# VHCDI.net
KiCad netlist of a schematic drawn in Altium Designer
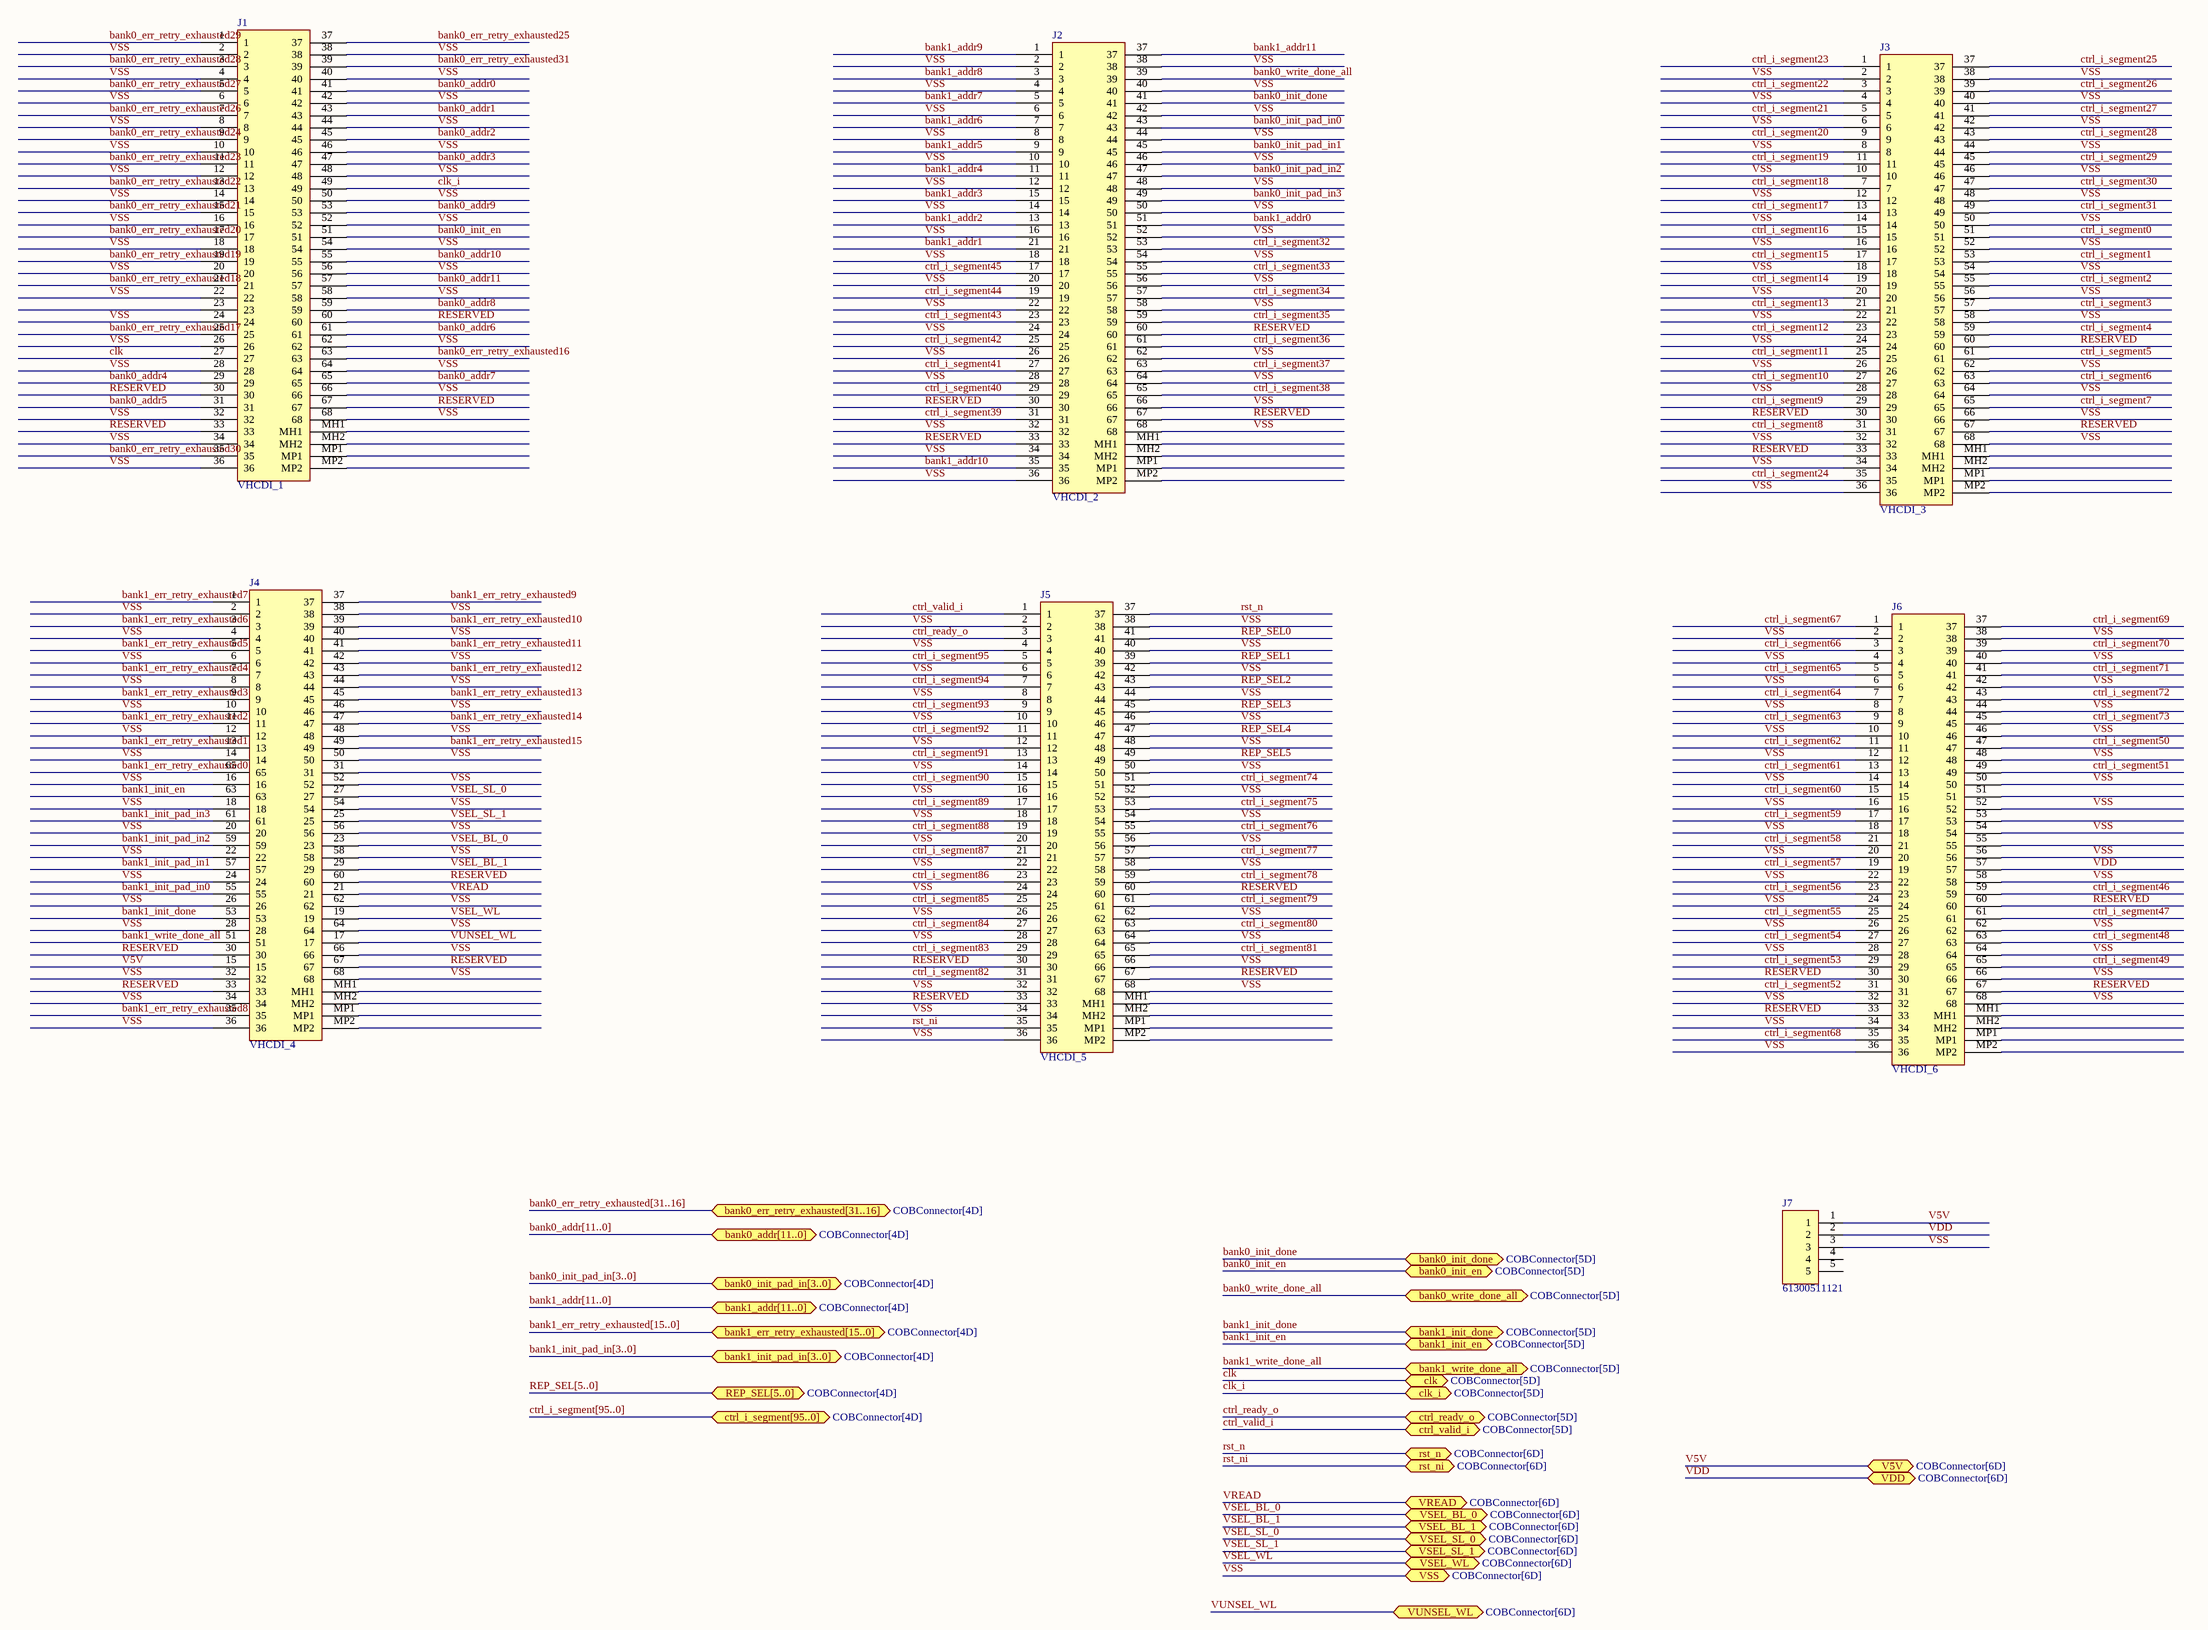
[diagram p0: VHCDI.SchDoc]

(export (version "E")
  (design (tool "Eeschema 10.0.6"))
  (components
    (comp (ref "J1")
      (value "VHCDI_1")
      (footprint "CONN68_HDRA-EC_HON")
      (description "Connector")
      (fields (field (name "MANUFACTURER_PART_NUMBER") "785633-01"))
      (libsource (lib "") (part "785633-01_2"))
    )
    (comp (ref "J2")
      (value "VHCDI_2")
      (footprint "CONN68_HDRA-EC_HON")
      (description "Connector")
      (fields (field (name "MANUFACTURER_PART_NUMBER") "785633-01"))
      (libsource (lib "") (part "785633-01_1"))
    )
    (comp (ref "J3")
      (value "VHCDI_3")
      (footprint "CONN68_HDRA-EC_HON")
      (description "Connector")
      (fields (field (name "MANUFACTURER_PART_NUMBER") "785633-01"))
      (libsource (lib "00-100001-001") (part "785633-01"))
    )
    (comp (ref "J4")
      (value "VHCDI_4")
      (footprint "CONN68_HDRA-EC_HON")
      (description "Connector")
      (fields (field (name "MANUFACTURER_PART_NUMBER") "785633-01"))
      (libsource (lib "") (part "785633-01_3"))
    )
    (comp (ref "J5")
      (value "VHCDI_5")
      (footprint "CONN68_HDRA-EC_HON")
      (description "Connector")
      (fields (field (name "MANUFACTURER_PART_NUMBER") "785633-01"))
      (libsource (lib "") (part "785633-01_4"))
    )
    (comp (ref "J6")
      (value "VHCDI_6")
      (footprint "CONN68_HDRA-EC_HON")
      (description "Connector")
      (fields (field (name "MANUFACTURER_PART_NUMBER") "785633-01"))
      (libsource (lib "") (part "785633-01_5"))
    )
    (comp (ref "J7")
      (value "61300511121")
      (footprint "HDRV5W64P0X254_1X5_1270X254X854P")
      (description "Connector")
      (fields (field (name "MOUSER PART NUMBER") "710-61300511121"))
      (libsource (lib "00-100001-001") (part "61300511121"))
    )
  )
  (nets
    (net (code "1") (name "/REP_SEL0") (class "Default")
      (node (ref "J5") (pin "41") (pinfunction "41_41") (pintype "passive"))
    )
    (net (code "2") (name "/REP_SEL1") (class "Default")
      (node (ref "J5") (pin "39") (pinfunction "39_39") (pintype "passive"))
    )
    (net (code "3") (name "/REP_SEL2") (class "Default")
      (node (ref "J5") (pin "43") (pinfunction "43_43") (pintype "passive"))
    )
    (net (code "4") (name "/REP_SEL3") (class "Default")
      (node (ref "J5") (pin "45") (pinfunction "45_45") (pintype "passive"))
    )
    (net (code "5") (name "/REP_SEL4") (class "Default")
      (node (ref "J5") (pin "47") (pinfunction "47_47") (pintype "passive"))
    )
    (net (code "6") (name "/REP_SEL5") (class "Default")
      (node (ref "J5") (pin "49") (pinfunction "49_49") (pintype "passive"))
    )
    (net (code "8") (name "/RESERVED") (class "Default")
      (node (ref "J1") (pin "30") (pinfunction "30_30") (pintype "passive"))
      (node (ref "J1") (pin "33") (pinfunction "33_33") (pintype "passive"))
      (node (ref "J1") (pin "60") (pinfunction "60_60") (pintype "passive"))
      (node (ref "J1") (pin "67") (pinfunction "67_67") (pintype "passive"))
      (node (ref "J2") (pin "30") (pinfunction "30_30") (pintype "passive"))
      (node (ref "J2") (pin "33") (pinfunction "33_33") (pintype "passive"))
      (node (ref "J2") (pin "60") (pinfunction "60_60") (pintype "passive"))
      (node (ref "J2") (pin "67") (pinfunction "67_67") (pintype "passive"))
      (node (ref "J3") (pin "30") (pinfunction "30_30") (pintype "passive"))
      (node (ref "J3") (pin "33") (pinfunction "33_33") (pintype "passive"))
      (node (ref "J3") (pin "60") (pinfunction "60_60") (pintype "passive"))
      (node (ref "J3") (pin "67") (pinfunction "67_67") (pintype "passive"))
      (node (ref "J4") (pin "30") (pinfunction "30_30") (pintype "passive"))
      (node (ref "J4") (pin "33") (pinfunction "33_33") (pintype "passive"))
      (node (ref "J4") (pin "60") (pinfunction "60_60") (pintype "passive"))
      (node (ref "J4") (pin "67") (pinfunction "67_67") (pintype "passive"))
      (node (ref "J5") (pin "30") (pinfunction "30_30") (pintype "passive"))
      (node (ref "J5") (pin "33") (pinfunction "33_33") (pintype "passive"))
      (node (ref "J5") (pin "60") (pinfunction "60_60") (pintype "passive"))
      (node (ref "J5") (pin "67") (pinfunction "67_67") (pintype "passive"))
      (node (ref "J6") (pin "30") (pinfunction "30_30") (pintype "passive"))
      (node (ref "J6") (pin "33") (pinfunction "33_33") (pintype "passive"))
      (node (ref "J6") (pin "60") (pinfunction "60_60") (pintype "passive"))
      (node (ref "J6") (pin "67") (pinfunction "67_67") (pintype "passive"))
    )
    (net (code "9") (name "/V5V") (class "Default")
      (node (ref "J4") (pin "15") (pinfunction "15_15") (pintype "passive"))
      (node (ref "J7") (pin "1") (pinfunction "1_1") (pintype "passive"))
    )
    (net (code "10") (name "/VDD") (class "Default")
      (node (ref "J6") (pin "57") (pinfunction "57_57") (pintype "passive"))
      (node (ref "J7") (pin "2") (pinfunction "2_2") (pintype "passive"))
    )
    (net (code "11") (name "/VREAD") (class "Default")
      (node (ref "J4") (pin "21") (pinfunction "21_21") (pintype "passive"))
    )
    (net (code "12") (name "/VSEL_BL_0") (class "Default")
      (node (ref "J4") (pin "23") (pinfunction "23_23") (pintype "passive"))
    )
    (net (code "13") (name "/VSEL_BL_1") (class "Default")
      (node (ref "J4") (pin "29") (pinfunction "29_29") (pintype "passive"))
    )
    (net (code "14") (name "/VSEL_SL_0") (class "Default")
      (node (ref "J4") (pin "27") (pinfunction "27_27") (pintype "passive"))
    )
    (net (code "15") (name "/VSEL_SL_1") (class "Default")
      (node (ref "J4") (pin "25") (pinfunction "25_25") (pintype "passive"))
    )
    (net (code "16") (name "/VSEL_WL") (class "Default")
      (node (ref "J4") (pin "19") (pinfunction "19_19") (pintype "passive"))
    )
    (net (code "17") (name "/VSS") (class "Default")
      (node (ref "J1") (pin "10") (pinfunction "10_10") (pintype "passive"))
      (node (ref "J1") (pin "12") (pinfunction "12_12") (pintype "passive"))
      (node (ref "J1") (pin "14") (pinfunction "14_14") (pintype "passive"))
      (node (ref "J1") (pin "16") (pinfunction "16_16") (pintype "passive"))
      (node (ref "J1") (pin "18") (pinfunction "18_18") (pintype "passive"))
      (node (ref "J1") (pin "2") (pinfunction "2_2") (pintype "passive"))
      (node (ref "J1") (pin "20") (pinfunction "20_20") (pintype "passive"))
      (node (ref "J1") (pin "22") (pinfunction "22_22") (pintype "passive"))
      (node (ref "J1") (pin "24") (pinfunction "24_24") (pintype "passive"))
      (node (ref "J1") (pin "26") (pinfunction "26_26") (pintype "passive"))
      (node (ref "J1") (pin "28") (pinfunction "28_28") (pintype "passive"))
      (node (ref "J1") (pin "32") (pinfunction "32_32") (pintype "passive"))
      (node (ref "J1") (pin "34") (pinfunction "34_34") (pintype "passive"))
      (node (ref "J1") (pin "36") (pinfunction "36_36") (pintype "passive"))
      (node (ref "J1") (pin "38") (pinfunction "38_38") (pintype "passive"))
      (node (ref "J1") (pin "4") (pinfunction "4_4") (pintype "passive"))
      (node (ref "J1") (pin "40") (pinfunction "40_40") (pintype "passive"))
      (node (ref "J1") (pin "42") (pinfunction "42_42") (pintype "passive"))
      (node (ref "J1") (pin "44") (pinfunction "44_44") (pintype "passive"))
      (node (ref "J1") (pin "46") (pinfunction "46_46") (pintype "passive"))
      (node (ref "J1") (pin "48") (pinfunction "48_48") (pintype "passive"))
      (node (ref "J1") (pin "50") (pinfunction "50_50") (pintype "passive"))
      (node (ref "J1") (pin "52") (pinfunction "52_52") (pintype "passive"))
      (node (ref "J1") (pin "54") (pinfunction "54_54") (pintype "passive"))
      (node (ref "J1") (pin "56") (pinfunction "56_56") (pintype "passive"))
      (node (ref "J1") (pin "58") (pinfunction "58_58") (pintype "passive"))
      (node (ref "J1") (pin "6") (pinfunction "6_6") (pintype "passive"))
      (node (ref "J1") (pin "62") (pinfunction "62_62") (pintype "passive"))
      (node (ref "J1") (pin "64") (pinfunction "64_64") (pintype "passive"))
      (node (ref "J1") (pin "66") (pinfunction "66_66") (pintype "passive"))
      (node (ref "J1") (pin "68") (pinfunction "68_68") (pintype "passive"))
      (node (ref "J1") (pin "8") (pinfunction "8_8") (pintype "passive"))
      (node (ref "J2") (pin "10") (pinfunction "10_10") (pintype "passive"))
      (node (ref "J2") (pin "12") (pinfunction "12_12") (pintype "passive"))
      (node (ref "J2") (pin "14") (pinfunction "14_14") (pintype "passive"))
      (node (ref "J2") (pin "16") (pinfunction "16_16") (pintype "passive"))
      (node (ref "J2") (pin "18") (pinfunction "18_18") (pintype "passive"))
      (node (ref "J2") (pin "2") (pinfunction "2_2") (pintype "passive"))
      (node (ref "J2") (pin "20") (pinfunction "20_20") (pintype "passive"))
      (node (ref "J2") (pin "22") (pinfunction "22_22") (pintype "passive"))
      (node (ref "J2") (pin "24") (pinfunction "24_24") (pintype "passive"))
      (node (ref "J2") (pin "26") (pinfunction "26_26") (pintype "passive"))
      (node (ref "J2") (pin "28") (pinfunction "28_28") (pintype "passive"))
      (node (ref "J2") (pin "32") (pinfunction "32_32") (pintype "passive"))
      (node (ref "J2") (pin "34") (pinfunction "34_34") (pintype "passive"))
      (node (ref "J2") (pin "36") (pinfunction "36_36") (pintype "passive"))
      (node (ref "J2") (pin "38") (pinfunction "38_38") (pintype "passive"))
      (node (ref "J2") (pin "4") (pinfunction "4_4") (pintype "passive"))
      (node (ref "J2") (pin "40") (pinfunction "40_40") (pintype "passive"))
      (node (ref "J2") (pin "42") (pinfunction "42_42") (pintype "passive"))
      (node (ref "J2") (pin "44") (pinfunction "44_44") (pintype "passive"))
      (node (ref "J2") (pin "46") (pinfunction "46_46") (pintype "passive"))
      (node (ref "J2") (pin "48") (pinfunction "48_48") (pintype "passive"))
      (node (ref "J2") (pin "50") (pinfunction "50_50") (pintype "passive"))
      (node (ref "J2") (pin "52") (pinfunction "52_52") (pintype "passive"))
      (node (ref "J2") (pin "54") (pinfunction "54_54") (pintype "passive"))
      (node (ref "J2") (pin "56") (pinfunction "56_56") (pintype "passive"))
      (node (ref "J2") (pin "58") (pinfunction "58_58") (pintype "passive"))
      (node (ref "J2") (pin "6") (pinfunction "6_6") (pintype "passive"))
      (node (ref "J2") (pin "62") (pinfunction "62_62") (pintype "passive"))
      (node (ref "J2") (pin "64") (pinfunction "64_64") (pintype "passive"))
      (node (ref "J2") (pin "66") (pinfunction "66_66") (pintype "passive"))
      (node (ref "J2") (pin "68") (pinfunction "68_68") (pintype "passive"))
      (node (ref "J2") (pin "8") (pinfunction "8_8") (pintype "passive"))
      (node (ref "J3") (pin "10") (pinfunction "10_10") (pintype "passive"))
      (node (ref "J3") (pin "12") (pinfunction "12_12") (pintype "passive"))
      (node (ref "J3") (pin "14") (pinfunction "14_14") (pintype "passive"))
      (node (ref "J3") (pin "16") (pinfunction "16_16") (pintype "passive"))
      (node (ref "J3") (pin "18") (pinfunction "18_18") (pintype "passive"))
      (node (ref "J3") (pin "2") (pinfunction "2_2") (pintype "passive"))
      (node (ref "J3") (pin "20") (pinfunction "20_20") (pintype "passive"))
      (node (ref "J3") (pin "22") (pinfunction "22_22") (pintype "passive"))
      (node (ref "J3") (pin "24") (pinfunction "24_24") (pintype "passive"))
      (node (ref "J3") (pin "26") (pinfunction "26_26") (pintype "passive"))
      (node (ref "J3") (pin "28") (pinfunction "28_28") (pintype "passive"))
      (node (ref "J3") (pin "32") (pinfunction "32_32") (pintype "passive"))
      (node (ref "J3") (pin "34") (pinfunction "34_34") (pintype "passive"))
      (node (ref "J3") (pin "36") (pinfunction "36_36") (pintype "passive"))
      (node (ref "J3") (pin "38") (pinfunction "38_38") (pintype "passive"))
      (node (ref "J3") (pin "4") (pinfunction "4_4") (pintype "passive"))
      (node (ref "J3") (pin "40") (pinfunction "40_40") (pintype "passive"))
      (node (ref "J3") (pin "42") (pinfunction "42_42") (pintype "passive"))
      (node (ref "J3") (pin "44") (pinfunction "44_44") (pintype "passive"))
      (node (ref "J3") (pin "46") (pinfunction "46_46") (pintype "passive"))
      (node (ref "J3") (pin "48") (pinfunction "48_48") (pintype "passive"))
      (node (ref "J3") (pin "50") (pinfunction "50_50") (pintype "passive"))
      (node (ref "J3") (pin "52") (pinfunction "52_52") (pintype "passive"))
      (node (ref "J3") (pin "54") (pinfunction "54_54") (pintype "passive"))
      (node (ref "J3") (pin "56") (pinfunction "56_56") (pintype "passive"))
      (node (ref "J3") (pin "58") (pinfunction "58_58") (pintype "passive"))
      (node (ref "J3") (pin "6") (pinfunction "6_6") (pintype "passive"))
      (node (ref "J3") (pin "62") (pinfunction "62_62") (pintype "passive"))
      (node (ref "J3") (pin "64") (pinfunction "64_64") (pintype "passive"))
      (node (ref "J3") (pin "66") (pinfunction "66_66") (pintype "passive"))
      (node (ref "J3") (pin "68") (pinfunction "68_68") (pintype "passive"))
      (node (ref "J3") (pin "8") (pinfunction "8_8") (pintype "passive"))
      (node (ref "J4") (pin "10") (pinfunction "10_10") (pintype "passive"))
      (node (ref "J4") (pin "12") (pinfunction "12_12") (pintype "passive"))
      (node (ref "J4") (pin "14") (pinfunction "14_14") (pintype "passive"))
      (node (ref "J4") (pin "16") (pinfunction "16_16") (pintype "passive"))
      (node (ref "J4") (pin "18") (pinfunction "18_18") (pintype "passive"))
      (node (ref "J4") (pin "2") (pinfunction "2_2") (pintype "passive"))
      (node (ref "J4") (pin "20") (pinfunction "20_20") (pintype "passive"))
      (node (ref "J4") (pin "22") (pinfunction "22_22") (pintype "passive"))
      (node (ref "J4") (pin "24") (pinfunction "24_24") (pintype "passive"))
      (node (ref "J4") (pin "26") (pinfunction "26_26") (pintype "passive"))
      (node (ref "J4") (pin "28") (pinfunction "28_28") (pintype "passive"))
      (node (ref "J4") (pin "32") (pinfunction "32_32") (pintype "passive"))
      (node (ref "J4") (pin "34") (pinfunction "34_34") (pintype "passive"))
      (node (ref "J4") (pin "36") (pinfunction "36_36") (pintype "passive"))
      (node (ref "J4") (pin "38") (pinfunction "38_38") (pintype "passive"))
      (node (ref "J4") (pin "4") (pinfunction "4_4") (pintype "passive"))
      (node (ref "J4") (pin "40") (pinfunction "40_40") (pintype "passive"))
      (node (ref "J4") (pin "42") (pinfunction "42_42") (pintype "passive"))
      (node (ref "J4") (pin "44") (pinfunction "44_44") (pintype "passive"))
      (node (ref "J4") (pin "46") (pinfunction "46_46") (pintype "passive"))
      (node (ref "J4") (pin "48") (pinfunction "48_48") (pintype "passive"))
      (node (ref "J4") (pin "50") (pinfunction "50_50") (pintype "passive"))
      (node (ref "J4") (pin "52") (pinfunction "52_52") (pintype "passive"))
      (node (ref "J4") (pin "54") (pinfunction "54_54") (pintype "passive"))
      (node (ref "J4") (pin "56") (pinfunction "56_56") (pintype "passive"))
      (node (ref "J4") (pin "58") (pinfunction "58_58") (pintype "passive"))
      (node (ref "J4") (pin "6") (pinfunction "6_6") (pintype "passive"))
      (node (ref "J4") (pin "62") (pinfunction "62_62") (pintype "passive"))
      (node (ref "J4") (pin "64") (pinfunction "64_64") (pintype "passive"))
      (node (ref "J4") (pin "66") (pinfunction "66_66") (pintype "passive"))
      (node (ref "J4") (pin "68") (pinfunction "68_68") (pintype "passive"))
      (node (ref "J4") (pin "8") (pinfunction "8_8") (pintype "passive"))
      (node (ref "J5") (pin "10") (pinfunction "10_10") (pintype "passive"))
      (node (ref "J5") (pin "12") (pinfunction "12_12") (pintype "passive"))
      (node (ref "J5") (pin "14") (pinfunction "14_14") (pintype "passive"))
      (node (ref "J5") (pin "16") (pinfunction "16_16") (pintype "passive"))
      (node (ref "J5") (pin "18") (pinfunction "18_18") (pintype "passive"))
      (node (ref "J5") (pin "2") (pinfunction "2_2") (pintype "passive"))
      (node (ref "J5") (pin "20") (pinfunction "20_20") (pintype "passive"))
      (node (ref "J5") (pin "22") (pinfunction "22_22") (pintype "passive"))
      (node (ref "J5") (pin "24") (pinfunction "24_24") (pintype "passive"))
      (node (ref "J5") (pin "26") (pinfunction "26_26") (pintype "passive"))
      (node (ref "J5") (pin "28") (pinfunction "28_28") (pintype "passive"))
      (node (ref "J5") (pin "32") (pinfunction "32_32") (pintype "passive"))
      (node (ref "J5") (pin "34") (pinfunction "34_34") (pintype "passive"))
      (node (ref "J5") (pin "36") (pinfunction "36_36") (pintype "passive"))
      (node (ref "J5") (pin "38") (pinfunction "38_38") (pintype "passive"))
      (node (ref "J5") (pin "4") (pinfunction "4_4") (pintype "passive"))
      (node (ref "J5") (pin "40") (pinfunction "40_40") (pintype "passive"))
      (node (ref "J5") (pin "42") (pinfunction "42_42") (pintype "passive"))
      (node (ref "J5") (pin "44") (pinfunction "44_44") (pintype "passive"))
      (node (ref "J5") (pin "46") (pinfunction "46_46") (pintype "passive"))
      (node (ref "J5") (pin "48") (pinfunction "48_48") (pintype "passive"))
      (node (ref "J5") (pin "50") (pinfunction "50_50") (pintype "passive"))
      (node (ref "J5") (pin "52") (pinfunction "52_52") (pintype "passive"))
      (node (ref "J5") (pin "54") (pinfunction "54_54") (pintype "passive"))
      (node (ref "J5") (pin "56") (pinfunction "56_56") (pintype "passive"))
      (node (ref "J5") (pin "58") (pinfunction "58_58") (pintype "passive"))
      (node (ref "J5") (pin "6") (pinfunction "6_6") (pintype "passive"))
      (node (ref "J5") (pin "62") (pinfunction "62_62") (pintype "passive"))
      (node (ref "J5") (pin "64") (pinfunction "64_64") (pintype "passive"))
      (node (ref "J5") (pin "66") (pinfunction "66_66") (pintype "passive"))
      (node (ref "J5") (pin "68") (pinfunction "68_68") (pintype "passive"))
      (node (ref "J5") (pin "8") (pinfunction "8_8") (pintype "passive"))
      (node (ref "J6") (pin "10") (pinfunction "10_10") (pintype "passive"))
      (node (ref "J6") (pin "12") (pinfunction "12_12") (pintype "passive"))
      (node (ref "J6") (pin "14") (pinfunction "14_14") (pintype "passive"))
      (node (ref "J6") (pin "16") (pinfunction "16_16") (pintype "passive"))
      (node (ref "J6") (pin "18") (pinfunction "18_18") (pintype "passive"))
      (node (ref "J6") (pin "2") (pinfunction "2_2") (pintype "passive"))
      (node (ref "J6") (pin "20") (pinfunction "20_20") (pintype "passive"))
      (node (ref "J6") (pin "22") (pinfunction "22_22") (pintype "passive"))
      (node (ref "J6") (pin "24") (pinfunction "24_24") (pintype "passive"))
      (node (ref "J6") (pin "26") (pinfunction "26_26") (pintype "passive"))
      (node (ref "J6") (pin "28") (pinfunction "28_28") (pintype "passive"))
      (node (ref "J6") (pin "32") (pinfunction "32_32") (pintype "passive"))
      (node (ref "J6") (pin "34") (pinfunction "34_34") (pintype "passive"))
      (node (ref "J6") (pin "36") (pinfunction "36_36") (pintype "passive"))
      (node (ref "J6") (pin "38") (pinfunction "38_38") (pintype "passive"))
      (node (ref "J6") (pin "4") (pinfunction "4_4") (pintype "passive"))
      (node (ref "J6") (pin "40") (pinfunction "40_40") (pintype "passive"))
      (node (ref "J6") (pin "42") (pinfunction "42_42") (pintype "passive"))
      (node (ref "J6") (pin "44") (pinfunction "44_44") (pintype "passive"))
      (node (ref "J6") (pin "46") (pinfunction "46_46") (pintype "passive"))
      (node (ref "J6") (pin "48") (pinfunction "48_48") (pintype "passive"))
      (node (ref "J6") (pin "50") (pinfunction "50_50") (pintype "passive"))
      (node (ref "J6") (pin "52") (pinfunction "52_52") (pintype "passive"))
      (node (ref "J6") (pin "54") (pinfunction "54_54") (pintype "passive"))
      (node (ref "J6") (pin "56") (pinfunction "56_56") (pintype "passive"))
      (node (ref "J6") (pin "58") (pinfunction "58_58") (pintype "passive"))
      (node (ref "J6") (pin "6") (pinfunction "6_6") (pintype "passive"))
      (node (ref "J6") (pin "62") (pinfunction "62_62") (pintype "passive"))
      (node (ref "J6") (pin "64") (pinfunction "64_64") (pintype "passive"))
      (node (ref "J6") (pin "66") (pinfunction "66_66") (pintype "passive"))
      (node (ref "J6") (pin "68") (pinfunction "68_68") (pintype "passive"))
      (node (ref "J6") (pin "8") (pinfunction "8_8") (pintype "passive"))
      (node (ref "J7") (pin "3") (pinfunction "3_3") (pintype "passive"))
    )
    (net (code "18") (name "/VUNSEL_WL") (class "Default")
      (node (ref "J4") (pin "17") (pinfunction "17_17") (pintype "passive"))
    )
    (net (code "19") (name "/bank0_addr0") (class "Default")
      (node (ref "J1") (pin "41") (pinfunction "41_41") (pintype "passive"))
    )
    (net (code "20") (name "/bank0_addr1") (class "Default")
      (node (ref "J1") (pin "43") (pinfunction "43_43") (pintype "passive"))
    )
    (net (code "21") (name "/bank0_addr2") (class "Default")
      (node (ref "J1") (pin "45") (pinfunction "45_45") (pintype "passive"))
    )
    (net (code "22") (name "/bank0_addr3") (class "Default")
      (node (ref "J1") (pin "47") (pinfunction "47_47") (pintype "passive"))
    )
    (net (code "23") (name "/bank0_addr4") (class "Default")
      (node (ref "J1") (pin "29") (pinfunction "29_29") (pintype "passive"))
    )
    (net (code "24") (name "/bank0_addr5") (class "Default")
      (node (ref "J1") (pin "31") (pinfunction "31_31") (pintype "passive"))
    )
    (net (code "25") (name "/bank0_addr6") (class "Default")
      (node (ref "J1") (pin "61") (pinfunction "61_61") (pintype "passive"))
    )
    (net (code "26") (name "/bank0_addr7") (class "Default")
      (node (ref "J1") (pin "65") (pinfunction "65_65") (pintype "passive"))
    )
    (net (code "27") (name "/bank0_addr8") (class "Default")
      (node (ref "J1") (pin "59") (pinfunction "59_59") (pintype "passive"))
    )
    (net (code "28") (name "/bank0_addr9") (class "Default")
      (node (ref "J1") (pin "53") (pinfunction "53_53") (pintype "passive"))
    )
    (net (code "29") (name "/bank0_addr10") (class "Default")
      (node (ref "J1") (pin "55") (pinfunction "55_55") (pintype "passive"))
    )
    (net (code "30") (name "/bank0_addr11") (class "Default")
      (node (ref "J1") (pin "57") (pinfunction "57_57") (pintype "passive"))
    )
    (net (code "32") (name "/bank0_err_retry_exhausted16") (class "Default")
      (node (ref "J1") (pin "63") (pinfunction "63_63") (pintype "passive"))
    )
    (net (code "33") (name "/bank0_err_retry_exhausted17") (class "Default")
      (node (ref "J1") (pin "25") (pinfunction "25_25") (pintype "passive"))
    )
    (net (code "34") (name "/bank0_err_retry_exhausted18") (class "Default")
      (node (ref "J1") (pin "21") (pinfunction "21_21") (pintype "passive"))
    )
    (net (code "35") (name "/bank0_err_retry_exhausted19") (class "Default")
      (node (ref "J1") (pin "19") (pinfunction "19_19") (pintype "passive"))
    )
    (net (code "36") (name "/bank0_err_retry_exhausted20") (class "Default")
      (node (ref "J1") (pin "17") (pinfunction "17_17") (pintype "passive"))
    )
    (net (code "37") (name "/bank0_err_retry_exhausted21") (class "Default")
      (node (ref "J1") (pin "15") (pinfunction "15_15") (pintype "passive"))
    )
    (net (code "38") (name "/bank0_err_retry_exhausted22") (class "Default")
      (node (ref "J1") (pin "13") (pinfunction "13_13") (pintype "passive"))
    )
    (net (code "39") (name "/bank0_err_retry_exhausted23") (class "Default")
      (node (ref "J1") (pin "11") (pinfunction "11_11") (pintype "passive"))
    )
    (net (code "40") (name "/bank0_err_retry_exhausted24") (class "Default")
      (node (ref "J1") (pin "9") (pinfunction "9_9") (pintype "passive"))
    )
    (net (code "41") (name "/bank0_err_retry_exhausted25") (class "Default")
      (node (ref "J1") (pin "37") (pinfunction "37_37") (pintype "passive"))
    )
    (net (code "42") (name "/bank0_err_retry_exhausted26") (class "Default")
      (node (ref "J1") (pin "7") (pinfunction "7_7") (pintype "passive"))
    )
    (net (code "43") (name "/bank0_err_retry_exhausted27") (class "Default")
      (node (ref "J1") (pin "5") (pinfunction "5_5") (pintype "passive"))
    )
    (net (code "44") (name "/bank0_err_retry_exhausted28") (class "Default")
      (node (ref "J1") (pin "3") (pinfunction "3_3") (pintype "passive"))
    )
    (net (code "45") (name "/bank0_err_retry_exhausted29") (class "Default")
      (node (ref "J1") (pin "1") (pinfunction "1_1") (pintype "passive"))
    )
    (net (code "46") (name "/bank0_err_retry_exhausted30") (class "Default")
      (node (ref "J1") (pin "35") (pinfunction "35_35") (pintype "passive"))
    )
    (net (code "47") (name "/bank0_err_retry_exhausted31") (class "Default")
      (node (ref "J1") (pin "39") (pinfunction "39_39") (pintype "passive"))
    )
    (net (code "49") (name "/bank0_init_done") (class "Default")
      (node (ref "J2") (pin "41") (pinfunction "41_41") (pintype "passive"))
    )
    (net (code "50") (name "/bank0_init_en") (class "Default")
      (node (ref "J1") (pin "51") (pinfunction "51_51") (pintype "passive"))
    )
    (net (code "51") (name "/bank0_init_pad_in0") (class "Default")
      (node (ref "J2") (pin "43") (pinfunction "43_43") (pintype "passive"))
    )
    (net (code "52") (name "/bank0_init_pad_in1") (class "Default")
      (node (ref "J2") (pin "45") (pinfunction "45_45") (pintype "passive"))
    )
    (net (code "53") (name "/bank0_init_pad_in2") (class "Default")
      (node (ref "J2") (pin "47") (pinfunction "47_47") (pintype "passive"))
    )
    (net (code "54") (name "/bank0_init_pad_in3") (class "Default")
      (node (ref "J2") (pin "49") (pinfunction "49_49") (pintype "passive"))
    )
    (net (code "56") (name "/bank0_write_done_all") (class "Default")
      (node (ref "J2") (pin "39") (pinfunction "39_39") (pintype "passive"))
    )
    (net (code "57") (name "/bank1_addr0") (class "Default")
      (node (ref "J2") (pin "51") (pinfunction "51_51") (pintype "passive"))
    )
    (net (code "58") (name "/bank1_addr1") (class "Default")
      (node (ref "J2") (pin "21") (pinfunction "21_21") (pintype "passive"))
    )
    (net (code "59") (name "/bank1_addr2") (class "Default")
      (node (ref "J2") (pin "13") (pinfunction "13_13") (pintype "passive"))
    )
    (net (code "60") (name "/bank1_addr3") (class "Default")
      (node (ref "J2") (pin "15") (pinfunction "15_15") (pintype "passive"))
    )
    (net (code "61") (name "/bank1_addr4") (class "Default")
      (node (ref "J2") (pin "11") (pinfunction "11_11") (pintype "passive"))
    )
    (net (code "62") (name "/bank1_addr5") (class "Default")
      (node (ref "J2") (pin "9") (pinfunction "9_9") (pintype "passive"))
    )
    (net (code "63") (name "/bank1_addr6") (class "Default")
      (node (ref "J2") (pin "7") (pinfunction "7_7") (pintype "passive"))
    )
    (net (code "64") (name "/bank1_addr7") (class "Default")
      (node (ref "J2") (pin "5") (pinfunction "5_5") (pintype "passive"))
    )
    (net (code "65") (name "/bank1_addr8") (class "Default")
      (node (ref "J2") (pin "3") (pinfunction "3_3") (pintype "passive"))
    )
    (net (code "66") (name "/bank1_addr9") (class "Default")
      (node (ref "J2") (pin "1") (pinfunction "1_1") (pintype "passive"))
    )
    (net (code "67") (name "/bank1_addr10") (class "Default")
      (node (ref "J2") (pin "35") (pinfunction "35_35") (pintype "passive"))
    )
    (net (code "68") (name "/bank1_addr11") (class "Default")
      (node (ref "J2") (pin "37") (pinfunction "37_37") (pintype "passive"))
    )
    (net (code "70") (name "/bank1_err_retry_exhausted0") (class "Default")
      (node (ref "J4") (pin "65") (pinfunction "65_65") (pintype "passive"))
    )
    (net (code "71") (name "/bank1_err_retry_exhausted1") (class "Default")
      (node (ref "J4") (pin "13") (pinfunction "13_13") (pintype "passive"))
    )
    (net (code "72") (name "/bank1_err_retry_exhausted2") (class "Default")
      (node (ref "J4") (pin "11") (pinfunction "11_11") (pintype "passive"))
    )
    (net (code "73") (name "/bank1_err_retry_exhausted3") (class "Default")
      (node (ref "J4") (pin "9") (pinfunction "9_9") (pintype "passive"))
    )
    (net (code "74") (name "/bank1_err_retry_exhausted4") (class "Default")
      (node (ref "J4") (pin "7") (pinfunction "7_7") (pintype "passive"))
    )
    (net (code "75") (name "/bank1_err_retry_exhausted5") (class "Default")
      (node (ref "J4") (pin "5") (pinfunction "5_5") (pintype "passive"))
    )
    (net (code "76") (name "/bank1_err_retry_exhausted6") (class "Default")
      (node (ref "J4") (pin "3") (pinfunction "3_3") (pintype "passive"))
    )
    (net (code "77") (name "/bank1_err_retry_exhausted7") (class "Default")
      (node (ref "J4") (pin "1") (pinfunction "1_1") (pintype "passive"))
    )
    (net (code "78") (name "/bank1_err_retry_exhausted8") (class "Default")
      (node (ref "J4") (pin "35") (pinfunction "35_35") (pintype "passive"))
    )
    (net (code "79") (name "/bank1_err_retry_exhausted9") (class "Default")
      (node (ref "J4") (pin "37") (pinfunction "37_37") (pintype "passive"))
    )
    (net (code "80") (name "/bank1_err_retry_exhausted10") (class "Default")
      (node (ref "J4") (pin "39") (pinfunction "39_39") (pintype "passive"))
    )
    (net (code "81") (name "/bank1_err_retry_exhausted11") (class "Default")
      (node (ref "J4") (pin "41") (pinfunction "41_41") (pintype "passive"))
    )
    (net (code "82") (name "/bank1_err_retry_exhausted12") (class "Default")
      (node (ref "J4") (pin "43") (pinfunction "43_43") (pintype "passive"))
    )
    (net (code "83") (name "/bank1_err_retry_exhausted13") (class "Default")
      (node (ref "J4") (pin "45") (pinfunction "45_45") (pintype "passive"))
    )
    (net (code "84") (name "/bank1_err_retry_exhausted14") (class "Default")
      (node (ref "J4") (pin "47") (pinfunction "47_47") (pintype "passive"))
    )
    (net (code "85") (name "/bank1_err_retry_exhausted15") (class "Default")
      (node (ref "J4") (pin "49") (pinfunction "49_49") (pintype "passive"))
    )
    (net (code "87") (name "/bank1_init_done") (class "Default")
      (node (ref "J4") (pin "53") (pinfunction "53_53") (pintype "passive"))
    )
    (net (code "88") (name "/bank1_init_en") (class "Default")
      (node (ref "J4") (pin "63") (pinfunction "63_63") (pintype "passive"))
    )
    (net (code "89") (name "/bank1_init_pad_in0") (class "Default")
      (node (ref "J4") (pin "55") (pinfunction "55_55") (pintype "passive"))
    )
    (net (code "90") (name "/bank1_init_pad_in1") (class "Default")
      (node (ref "J4") (pin "57") (pinfunction "57_57") (pintype "passive"))
    )
    (net (code "91") (name "/bank1_init_pad_in2") (class "Default")
      (node (ref "J4") (pin "59") (pinfunction "59_59") (pintype "passive"))
    )
    (net (code "92") (name "/bank1_init_pad_in3") (class "Default")
      (node (ref "J4") (pin "61") (pinfunction "61_61") (pintype "passive"))
    )
    (net (code "94") (name "/bank1_write_done_all") (class "Default")
      (node (ref "J4") (pin "51") (pinfunction "51_51") (pintype "passive"))
    )
    (net (code "95") (name "/clk") (class "Default")
      (node (ref "J1") (pin "27") (pinfunction "27_27") (pintype "passive"))
    )
    (net (code "96") (name "/clk_i") (class "Default")
      (node (ref "J1") (pin "49") (pinfunction "49_49") (pintype "passive"))
    )
    (net (code "97") (name "/ctrl_i_segment0") (class "Default")
      (node (ref "J3") (pin "51") (pinfunction "51_51") (pintype "passive"))
    )
    (net (code "98") (name "/ctrl_i_segment1") (class "Default")
      (node (ref "J3") (pin "53") (pinfunction "53_53") (pintype "passive"))
    )
    (net (code "99") (name "/ctrl_i_segment2") (class "Default")
      (node (ref "J3") (pin "55") (pinfunction "55_55") (pintype "passive"))
    )
    (net (code "100") (name "/ctrl_i_segment3") (class "Default")
      (node (ref "J3") (pin "57") (pinfunction "57_57") (pintype "passive"))
    )
    (net (code "101") (name "/ctrl_i_segment4") (class "Default")
      (node (ref "J3") (pin "59") (pinfunction "59_59") (pintype "passive"))
    )
    (net (code "102") (name "/ctrl_i_segment5") (class "Default")
      (node (ref "J3") (pin "61") (pinfunction "61_61") (pintype "passive"))
    )
    (net (code "103") (name "/ctrl_i_segment6") (class "Default")
      (node (ref "J3") (pin "63") (pinfunction "63_63") (pintype "passive"))
    )
    (net (code "104") (name "/ctrl_i_segment7") (class "Default")
      (node (ref "J3") (pin "65") (pinfunction "65_65") (pintype "passive"))
    )
    (net (code "105") (name "/ctrl_i_segment8") (class "Default")
      (node (ref "J3") (pin "31") (pinfunction "31_31") (pintype "passive"))
    )
    (net (code "106") (name "/ctrl_i_segment9") (class "Default")
      (node (ref "J3") (pin "29") (pinfunction "29_29") (pintype "passive"))
    )
    (net (code "107") (name "/ctrl_i_segment10") (class "Default")
      (node (ref "J3") (pin "27") (pinfunction "27_27") (pintype "passive"))
    )
    (net (code "108") (name "/ctrl_i_segment11") (class "Default")
      (node (ref "J3") (pin "25") (pinfunction "25_25") (pintype "passive"))
    )
    (net (code "109") (name "/ctrl_i_segment12") (class "Default")
      (node (ref "J3") (pin "23") (pinfunction "23_23") (pintype "passive"))
    )
    (net (code "110") (name "/ctrl_i_segment13") (class "Default")
      (node (ref "J3") (pin "21") (pinfunction "21_21") (pintype "passive"))
    )
    (net (code "111") (name "/ctrl_i_segment14") (class "Default")
      (node (ref "J3") (pin "19") (pinfunction "19_19") (pintype "passive"))
    )
    (net (code "112") (name "/ctrl_i_segment15") (class "Default")
      (node (ref "J3") (pin "17") (pinfunction "17_17") (pintype "passive"))
    )
    (net (code "113") (name "/ctrl_i_segment16") (class "Default")
      (node (ref "J3") (pin "15") (pinfunction "15_15") (pintype "passive"))
    )
    (net (code "114") (name "/ctrl_i_segment17") (class "Default")
      (node (ref "J3") (pin "13") (pinfunction "13_13") (pintype "passive"))
    )
    (net (code "115") (name "/ctrl_i_segment18") (class "Default")
      (node (ref "J3") (pin "7") (pinfunction "7_7") (pintype "passive"))
    )
    (net (code "116") (name "/ctrl_i_segment19") (class "Default")
      (node (ref "J3") (pin "11") (pinfunction "11_11") (pintype "passive"))
    )
    (net (code "117") (name "/ctrl_i_segment20") (class "Default")
      (node (ref "J3") (pin "9") (pinfunction "9_9") (pintype "passive"))
    )
    (net (code "118") (name "/ctrl_i_segment21") (class "Default")
      (node (ref "J3") (pin "5") (pinfunction "5_5") (pintype "passive"))
    )
    (net (code "119") (name "/ctrl_i_segment22") (class "Default")
      (node (ref "J3") (pin "3") (pinfunction "3_3") (pintype "passive"))
    )
    (net (code "120") (name "/ctrl_i_segment23") (class "Default")
      (node (ref "J3") (pin "1") (pinfunction "1_1") (pintype "passive"))
    )
    (net (code "121") (name "/ctrl_i_segment24") (class "Default")
      (node (ref "J3") (pin "35") (pinfunction "35_35") (pintype "passive"))
    )
    (net (code "122") (name "/ctrl_i_segment25") (class "Default")
      (node (ref "J3") (pin "37") (pinfunction "37_37") (pintype "passive"))
    )
    (net (code "123") (name "/ctrl_i_segment26") (class "Default")
      (node (ref "J3") (pin "39") (pinfunction "39_39") (pintype "passive"))
    )
    (net (code "124") (name "/ctrl_i_segment27") (class "Default")
      (node (ref "J3") (pin "41") (pinfunction "41_41") (pintype "passive"))
    )
    (net (code "125") (name "/ctrl_i_segment28") (class "Default")
      (node (ref "J3") (pin "43") (pinfunction "43_43") (pintype "passive"))
    )
    (net (code "126") (name "/ctrl_i_segment29") (class "Default")
      (node (ref "J3") (pin "45") (pinfunction "45_45") (pintype "passive"))
    )
    (net (code "127") (name "/ctrl_i_segment30") (class "Default")
      (node (ref "J3") (pin "47") (pinfunction "47_47") (pintype "passive"))
    )
    (net (code "128") (name "/ctrl_i_segment31") (class "Default")
      (node (ref "J3") (pin "49") (pinfunction "49_49") (pintype "passive"))
    )
    (net (code "129") (name "/ctrl_i_segment32") (class "Default")
      (node (ref "J2") (pin "53") (pinfunction "53_53") (pintype "passive"))
    )
    (net (code "130") (name "/ctrl_i_segment33") (class "Default")
      (node (ref "J2") (pin "55") (pinfunction "55_55") (pintype "passive"))
    )
    (net (code "131") (name "/ctrl_i_segment34") (class "Default")
      (node (ref "J2") (pin "57") (pinfunction "57_57") (pintype "passive"))
    )
    (net (code "132") (name "/ctrl_i_segment35") (class "Default")
      (node (ref "J2") (pin "59") (pinfunction "59_59") (pintype "passive"))
    )
    (net (code "133") (name "/ctrl_i_segment36") (class "Default")
      (node (ref "J2") (pin "61") (pinfunction "61_61") (pintype "passive"))
    )
    (net (code "134") (name "/ctrl_i_segment37") (class "Default")
      (node (ref "J2") (pin "63") (pinfunction "63_63") (pintype "passive"))
    )
    (net (code "135") (name "/ctrl_i_segment38") (class "Default")
      (node (ref "J2") (pin "65") (pinfunction "65_65") (pintype "passive"))
    )
    (net (code "136") (name "/ctrl_i_segment39") (class "Default")
      (node (ref "J2") (pin "31") (pinfunction "31_31") (pintype "passive"))
    )
    (net (code "137") (name "/ctrl_i_segment40") (class "Default")
      (node (ref "J2") (pin "29") (pinfunction "29_29") (pintype "passive"))
    )
    (net (code "138") (name "/ctrl_i_segment41") (class "Default")
      (node (ref "J2") (pin "27") (pinfunction "27_27") (pintype "passive"))
    )
    (net (code "139") (name "/ctrl_i_segment42") (class "Default")
      (node (ref "J2") (pin "25") (pinfunction "25_25") (pintype "passive"))
    )
    (net (code "140") (name "/ctrl_i_segment43") (class "Default")
      (node (ref "J2") (pin "23") (pinfunction "23_23") (pintype "passive"))
    )
    (net (code "141") (name "/ctrl_i_segment44") (class "Default")
      (node (ref "J2") (pin "19") (pinfunction "19_19") (pintype "passive"))
    )
    (net (code "142") (name "/ctrl_i_segment45") (class "Default")
      (node (ref "J2") (pin "17") (pinfunction "17_17") (pintype "passive"))
    )
    (net (code "143") (name "/ctrl_i_segment46") (class "Default")
      (node (ref "J6") (pin "59") (pinfunction "59_59") (pintype "passive"))
    )
    (net (code "144") (name "/ctrl_i_segment47") (class "Default")
      (node (ref "J6") (pin "61") (pinfunction "61_61") (pintype "passive"))
    )
    (net (code "145") (name "/ctrl_i_segment48") (class "Default")
      (node (ref "J6") (pin "63") (pinfunction "63_63") (pintype "passive"))
    )
    (net (code "146") (name "/ctrl_i_segment49") (class "Default")
      (node (ref "J6") (pin "65") (pinfunction "65_65") (pintype "passive"))
    )
    (net (code "147") (name "/ctrl_i_segment50") (class "Default")
      (node (ref "J6") (pin "47") (pinfunction "47_47") (pintype "passive"))
    )
    (net (code "148") (name "/ctrl_i_segment51") (class "Default")
      (node (ref "J6") (pin "49") (pinfunction "49_49") (pintype "passive"))
    )
    (net (code "149") (name "/ctrl_i_segment52") (class "Default")
      (node (ref "J6") (pin "31") (pinfunction "31_31") (pintype "passive"))
    )
    (net (code "150") (name "/ctrl_i_segment53") (class "Default")
      (node (ref "J6") (pin "29") (pinfunction "29_29") (pintype "passive"))
    )
    (net (code "151") (name "/ctrl_i_segment54") (class "Default")
      (node (ref "J6") (pin "27") (pinfunction "27_27") (pintype "passive"))
    )
    (net (code "152") (name "/ctrl_i_segment55") (class "Default")
      (node (ref "J6") (pin "25") (pinfunction "25_25") (pintype "passive"))
    )
    (net (code "153") (name "/ctrl_i_segment56") (class "Default")
      (node (ref "J6") (pin "23") (pinfunction "23_23") (pintype "passive"))
    )
    (net (code "154") (name "/ctrl_i_segment57") (class "Default")
      (node (ref "J6") (pin "19") (pinfunction "19_19") (pintype "passive"))
    )
    (net (code "155") (name "/ctrl_i_segment58") (class "Default")
      (node (ref "J6") (pin "21") (pinfunction "21_21") (pintype "passive"))
    )
    (net (code "156") (name "/ctrl_i_segment59") (class "Default")
      (node (ref "J6") (pin "17") (pinfunction "17_17") (pintype "passive"))
    )
    (net (code "157") (name "/ctrl_i_segment60") (class "Default")
      (node (ref "J6") (pin "15") (pinfunction "15_15") (pintype "passive"))
    )
    (net (code "158") (name "/ctrl_i_segment61") (class "Default")
      (node (ref "J6") (pin "13") (pinfunction "13_13") (pintype "passive"))
    )
    (net (code "159") (name "/ctrl_i_segment62") (class "Default")
      (node (ref "J6") (pin "11") (pinfunction "11_11") (pintype "passive"))
    )
    (net (code "160") (name "/ctrl_i_segment63") (class "Default")
      (node (ref "J6") (pin "9") (pinfunction "9_9") (pintype "passive"))
    )
    (net (code "161") (name "/ctrl_i_segment64") (class "Default")
      (node (ref "J6") (pin "7") (pinfunction "7_7") (pintype "passive"))
    )
    (net (code "162") (name "/ctrl_i_segment65") (class "Default")
      (node (ref "J6") (pin "5") (pinfunction "5_5") (pintype "passive"))
    )
    (net (code "163") (name "/ctrl_i_segment66") (class "Default")
      (node (ref "J6") (pin "3") (pinfunction "3_3") (pintype "passive"))
    )
    (net (code "164") (name "/ctrl_i_segment67") (class "Default")
      (node (ref "J6") (pin "1") (pinfunction "1_1") (pintype "passive"))
    )
    (net (code "165") (name "/ctrl_i_segment68") (class "Default")
      (node (ref "J6") (pin "35") (pinfunction "35_35") (pintype "passive"))
    )
    (net (code "166") (name "/ctrl_i_segment69") (class "Default")
      (node (ref "J6") (pin "37") (pinfunction "37_37") (pintype "passive"))
    )
    (net (code "167") (name "/ctrl_i_segment70") (class "Default")
      (node (ref "J6") (pin "39") (pinfunction "39_39") (pintype "passive"))
    )
    (net (code "168") (name "/ctrl_i_segment71") (class "Default")
      (node (ref "J6") (pin "41") (pinfunction "41_41") (pintype "passive"))
    )
    (net (code "169") (name "/ctrl_i_segment72") (class "Default")
      (node (ref "J6") (pin "43") (pinfunction "43_43") (pintype "passive"))
    )
    (net (code "170") (name "/ctrl_i_segment73") (class "Default")
      (node (ref "J6") (pin "45") (pinfunction "45_45") (pintype "passive"))
    )
    (net (code "171") (name "/ctrl_i_segment74") (class "Default")
      (node (ref "J5") (pin "51") (pinfunction "51_51") (pintype "passive"))
    )
    (net (code "172") (name "/ctrl_i_segment75") (class "Default")
      (node (ref "J5") (pin "53") (pinfunction "53_53") (pintype "passive"))
    )
    (net (code "173") (name "/ctrl_i_segment76") (class "Default")
      (node (ref "J5") (pin "55") (pinfunction "55_55") (pintype "passive"))
    )
    (net (code "174") (name "/ctrl_i_segment77") (class "Default")
      (node (ref "J5") (pin "57") (pinfunction "57_57") (pintype "passive"))
    )
    (net (code "175") (name "/ctrl_i_segment78") (class "Default")
      (node (ref "J5") (pin "59") (pinfunction "59_59") (pintype "passive"))
    )
    (net (code "176") (name "/ctrl_i_segment79") (class "Default")
      (node (ref "J5") (pin "61") (pinfunction "61_61") (pintype "passive"))
    )
    (net (code "177") (name "/ctrl_i_segment80") (class "Default")
      (node (ref "J5") (pin "63") (pinfunction "63_63") (pintype "passive"))
    )
    (net (code "178") (name "/ctrl_i_segment81") (class "Default")
      (node (ref "J5") (pin "65") (pinfunction "65_65") (pintype "passive"))
    )
    (net (code "179") (name "/ctrl_i_segment82") (class "Default")
      (node (ref "J5") (pin "31") (pinfunction "31_31") (pintype "passive"))
    )
    (net (code "180") (name "/ctrl_i_segment83") (class "Default")
      (node (ref "J5") (pin "29") (pinfunction "29_29") (pintype "passive"))
    )
    (net (code "181") (name "/ctrl_i_segment84") (class "Default")
      (node (ref "J5") (pin "27") (pinfunction "27_27") (pintype "passive"))
    )
    (net (code "182") (name "/ctrl_i_segment85") (class "Default")
      (node (ref "J5") (pin "25") (pinfunction "25_25") (pintype "passive"))
    )
    (net (code "183") (name "/ctrl_i_segment86") (class "Default")
      (node (ref "J5") (pin "23") (pinfunction "23_23") (pintype "passive"))
    )
    (net (code "184") (name "/ctrl_i_segment87") (class "Default")
      (node (ref "J5") (pin "21") (pinfunction "21_21") (pintype "passive"))
    )
    (net (code "185") (name "/ctrl_i_segment88") (class "Default")
      (node (ref "J5") (pin "19") (pinfunction "19_19") (pintype "passive"))
    )
    (net (code "186") (name "/ctrl_i_segment89") (class "Default")
      (node (ref "J5") (pin "17") (pinfunction "17_17") (pintype "passive"))
    )
    (net (code "187") (name "/ctrl_i_segment90") (class "Default")
      (node (ref "J5") (pin "15") (pinfunction "15_15") (pintype "passive"))
    )
    (net (code "188") (name "/ctrl_i_segment91") (class "Default")
      (node (ref "J5") (pin "13") (pinfunction "13_13") (pintype "passive"))
    )
    (net (code "189") (name "/ctrl_i_segment92") (class "Default")
      (node (ref "J5") (pin "11") (pinfunction "11_11") (pintype "passive"))
    )
    (net (code "190") (name "/ctrl_i_segment93") (class "Default")
      (node (ref "J5") (pin "9") (pinfunction "9_9") (pintype "passive"))
    )
    (net (code "191") (name "/ctrl_i_segment94") (class "Default")
      (node (ref "J5") (pin "7") (pinfunction "7_7") (pintype "passive"))
    )
    (net (code "192") (name "/ctrl_i_segment95") (class "Default")
      (node (ref "J5") (pin "5") (pinfunction "5_5") (pintype "passive"))
    )
    (net (code "194") (name "/ctrl_ready_o") (class "Default")
      (node (ref "J5") (pin "3") (pinfunction "3_3") (pintype "passive"))
    )
    (net (code "195") (name "/ctrl_valid_i") (class "Default")
      (node (ref "J5") (pin "1") (pinfunction "1_1") (pintype "passive"))
    )
    (net (code "196") (name "/rst_n") (class "Default")
      (node (ref "J5") (pin "37") (pinfunction "37_37") (pintype "passive"))
    )
    (net (code "197") (name "/rst_ni") (class "Default")
      (node (ref "J5") (pin "35") (pinfunction "35_35") (pintype "passive"))
    )
    (net (code "198") (name "unconnected-(J1-Pad23)") (class "Default")
      (node (ref "J1") (pin "23") (pinfunction "23_23") (pintype "passive"))
    )
    (net (code "199") (name "unconnected-(J1-PadMH1)") (class "Default")
      (node (ref "J1") (pin "MH1") (pinfunction "MH1_MH1") (pintype "passive"))
    )
    (net (code "200") (name "unconnected-(J1-PadMH2)") (class "Default")
      (node (ref "J1") (pin "MH2") (pinfunction "MH2_MH2") (pintype "passive"))
    )
    (net (code "201") (name "unconnected-(J1-PadMP1)") (class "Default")
      (node (ref "J1") (pin "MP1") (pinfunction "MP1_MP1") (pintype "passive"))
    )
    (net (code "202") (name "unconnected-(J1-PadMP2)") (class "Default")
      (node (ref "J1") (pin "MP2") (pinfunction "MP2_MP2") (pintype "passive"))
    )
    (net (code "203") (name "unconnected-(J2-PadMH1)") (class "Default")
      (node (ref "J2") (pin "MH1") (pinfunction "MH1_MH1") (pintype "passive"))
    )
    (net (code "204") (name "unconnected-(J2-PadMH2)") (class "Default")
      (node (ref "J2") (pin "MH2") (pinfunction "MH2_MH2") (pintype "passive"))
    )
    (net (code "205") (name "unconnected-(J2-PadMP1)") (class "Default")
      (node (ref "J2") (pin "MP1") (pinfunction "MP1_MP1") (pintype "passive"))
    )
    (net (code "206") (name "unconnected-(J2-PadMP2)") (class "Default")
      (node (ref "J2") (pin "MP2") (pinfunction "MP2_MP2") (pintype "passive"))
    )
    (net (code "207") (name "unconnected-(J3-PadMH1)") (class "Default")
      (node (ref "J3") (pin "MH1") (pinfunction "MH1_MH1") (pintype "passive"))
    )
    (net (code "208") (name "unconnected-(J3-PadMH2)") (class "Default")
      (node (ref "J3") (pin "MH2") (pinfunction "MH2_MH2") (pintype "passive"))
    )
    (net (code "209") (name "unconnected-(J3-PadMP1)") (class "Default")
      (node (ref "J3") (pin "MP1") (pinfunction "MP1_MP1") (pintype "passive"))
    )
    (net (code "210") (name "unconnected-(J3-PadMP2)") (class "Default")
      (node (ref "J3") (pin "MP2") (pinfunction "MP2_MP2") (pintype "passive"))
    )
    (net (code "211") (name "unconnected-(J4-Pad31)") (class "Default")
      (node (ref "J4") (pin "31") (pinfunction "31_31") (pintype "passive"))
    )
    (net (code "212") (name "unconnected-(J4-PadMH1)") (class "Default")
      (node (ref "J4") (pin "MH1") (pinfunction "MH1_MH1") (pintype "passive"))
    )
    (net (code "213") (name "unconnected-(J4-PadMH2)") (class "Default")
      (node (ref "J4") (pin "MH2") (pinfunction "MH2_MH2") (pintype "passive"))
    )
    (net (code "214") (name "unconnected-(J4-PadMP1)") (class "Default")
      (node (ref "J4") (pin "MP1") (pinfunction "MP1_MP1") (pintype "passive"))
    )
    (net (code "215") (name "unconnected-(J4-PadMP2)") (class "Default")
      (node (ref "J4") (pin "MP2") (pinfunction "MP2_MP2") (pintype "passive"))
    )
    (net (code "216") (name "unconnected-(J5-PadMH1)") (class "Default")
      (node (ref "J5") (pin "MH1") (pinfunction "MH1_MH1") (pintype "passive"))
    )
    (net (code "217") (name "unconnected-(J5-PadMH2)") (class "Default")
      (node (ref "J5") (pin "MH2") (pinfunction "MH2_MH2") (pintype "passive"))
    )
    (net (code "218") (name "unconnected-(J5-PadMP1)") (class "Default")
      (node (ref "J5") (pin "MP1") (pinfunction "MP1_MP1") (pintype "passive"))
    )
    (net (code "219") (name "unconnected-(J5-PadMP2)") (class "Default")
      (node (ref "J5") (pin "MP2") (pinfunction "MP2_MP2") (pintype "passive"))
    )
    (net (code "220") (name "unconnected-(J6-Pad51)") (class "Default")
      (node (ref "J6") (pin "51") (pinfunction "51_51") (pintype "passive"))
    )
    (net (code "221") (name "unconnected-(J6-Pad53)") (class "Default")
      (node (ref "J6") (pin "53") (pinfunction "53_53") (pintype "passive"))
    )
    (net (code "222") (name "unconnected-(J6-Pad55)") (class "Default")
      (node (ref "J6") (pin "55") (pinfunction "55_55") (pintype "passive"))
    )
    (net (code "223") (name "unconnected-(J6-PadMH1)") (class "Default")
      (node (ref "J6") (pin "MH1") (pinfunction "MH1_MH1") (pintype "passive"))
    )
    (net (code "224") (name "unconnected-(J6-PadMH2)") (class "Default")
      (node (ref "J6") (pin "MH2") (pinfunction "MH2_MH2") (pintype "passive"))
    )
    (net (code "225") (name "unconnected-(J6-PadMP1)") (class "Default")
      (node (ref "J6") (pin "MP1") (pinfunction "MP1_MP1") (pintype "passive"))
    )
    (net (code "226") (name "unconnected-(J6-PadMP2)") (class "Default")
      (node (ref "J6") (pin "MP2") (pinfunction "MP2_MP2") (pintype "passive"))
    )
    (net (code "227") (name "unconnected-(J7-Pad4)") (class "Default")
      (node (ref "J7") (pin "4") (pinfunction "4_4") (pintype "passive"))
    )
    (net (code "228") (name "unconnected-(J7-Pad5)") (class "Default")
      (node (ref "J7") (pin "5") (pinfunction "5_5") (pintype "passive"))
    )
  )
)
